# ESP_LoRa_Weather.net
KiCad netlist of a schematic drawn in EAGLE
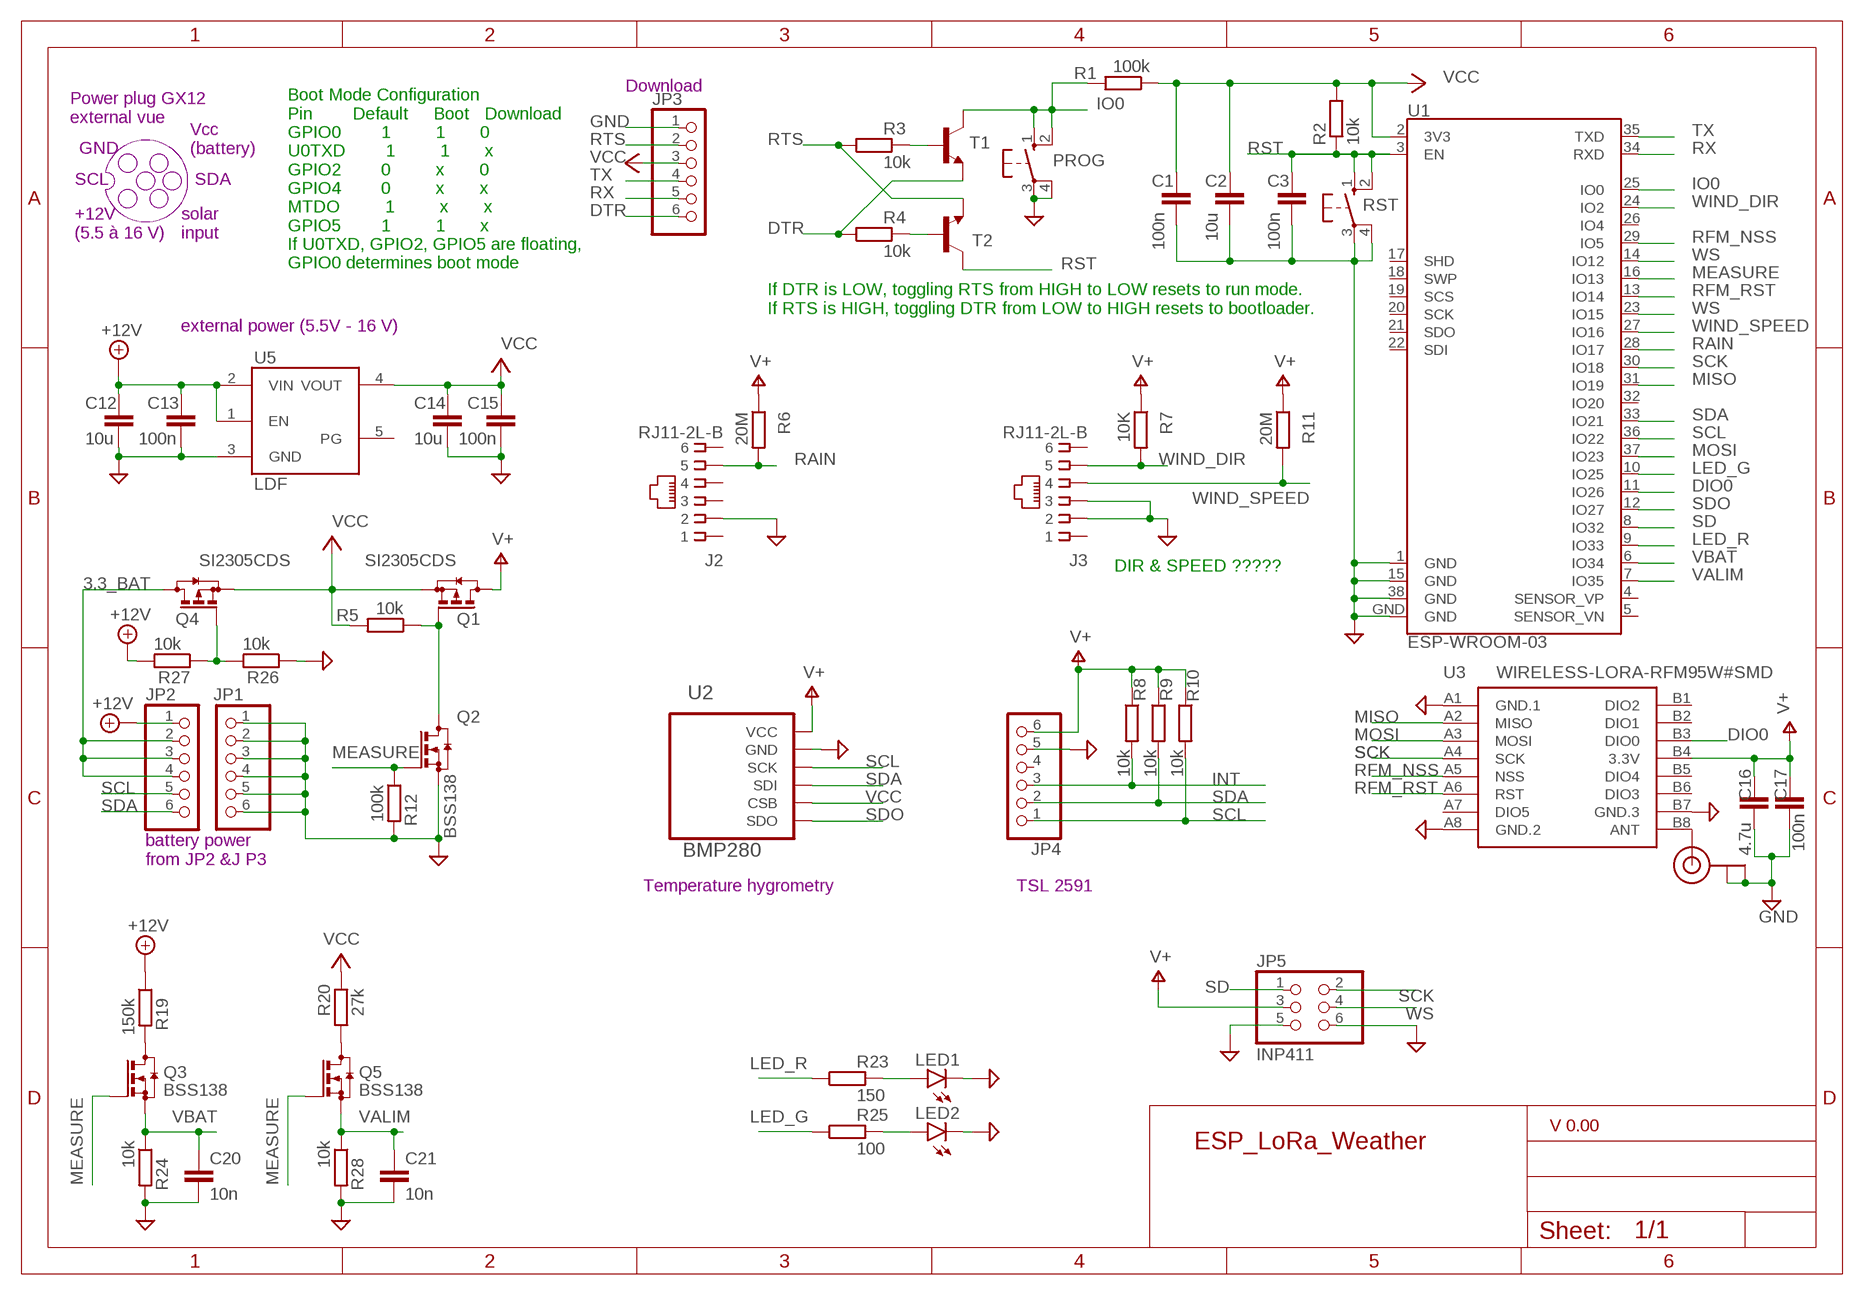
[diagram p0: schematic, sheet 1]

(export (version "E")
  (design (tool "Eeschema 10.0.6"))
  (components
    (comp (ref "C1")
      (value "100n")
      (footprint "eagle-import:C1206")
      (libsource (lib "eagle-import") (part "CC1206"))
    )
    (comp (ref "C2")
      (value "10u")
      (footprint "eagle-import:C1210")
      (libsource (lib "eagle-import") (part "CC1210"))
    )
    (comp (ref "C3")
      (value "100n")
      (footprint "eagle-import:C1206")
      (libsource (lib "eagle-import") (part "CC1206"))
    )
    (comp (ref "C12")
      (value "10u")
      (footprint "eagle-import:C1210")
      (libsource (lib "eagle-import") (part "CC1210"))
    )
    (comp (ref "C13")
      (value "100n")
      (footprint "eagle-import:C1206")
      (libsource (lib "eagle-import") (part "CC1206"))
    )
    (comp (ref "C14")
      (value "10u")
      (footprint "eagle-import:C1210")
      (libsource (lib "eagle-import") (part "CC1210"))
    )
    (comp (ref "C15")
      (value "100n")
      (footprint "eagle-import:C1206")
      (libsource (lib "eagle-import") (part "CC1206"))
    )
    (comp (ref "C16")
      (value "4.7u")
      (footprint "eagle-import:C1210")
      (libsource (lib "eagle-import") (part "CC1210"))
    )
    (comp (ref "C17")
      (value "100n")
      (footprint "eagle-import:C1206")
      (libsource (lib "eagle-import") (part "CC1206"))
    )
    (comp (ref "C20")
      (value "10n")
      (footprint "eagle-import:C1206")
      (libsource (lib "eagle-import") (part "CC1206"))
    )
    (comp (ref "C21")
      (value "10n")
      (footprint "eagle-import:C1206")
      (libsource (lib "eagle-import") (part "CC1206"))
    )
    (comp (ref "J1")
      (value "U.FL")
      (footprint "eagle-import:U.FL")
      (libsource (lib "eagle-import") (part "U.FL"))
    )
    (comp (ref "J2")
      (value "RJ11-2L-B")
      (footprint "eagle-import:RJ11-NO_SHIELD")
      (fields (field (name "MF") "TYCO ELECTRONICS"))
      (libsource (lib "eagle-import") (part "RJ11-2L-B"))
    )
    (comp (ref "J3")
      (value "RJ11-2L-B")
      (footprint "eagle-import:RJ11-NO_SHIELD")
      (fields (field (name "MF") "TYCO ELECTRONICS"))
      (libsource (lib "eagle-import") (part "RJ11-2L-B"))
    )
    (comp (ref "JP1")
      (value "PINHD-1X6")
      (footprint "eagle-import:1X06")
      (libsource (lib "eagle-import") (part "PINHD-1X6"))
    )
    (comp (ref "JP2")
      (value "PINHD-1X6")
      (footprint "eagle-import:1X06")
      (libsource (lib "eagle-import") (part "PINHD-1X6"))
    )
    (comp (ref "JP3")
      (value "PINHD-1X6")
      (footprint "eagle-import:1X06")
      (libsource (lib "eagle-import") (part "PINHD-1X6"))
    )
    (comp (ref "JP4")
      (value "PINHD-1X6")
      (footprint "eagle-import:1X06")
      (libsource (lib "eagle-import") (part "PINHD-1X6"))
    )
    (comp (ref "JP5")
      (value "INP411")
      (footprint "eagle-import:2X03")
      (libsource (lib "eagle-import") (part "PINHD-2X3"))
    )
    (comp (ref "LED1")
      (value "LEDCHIPLED_0805")
      (footprint "eagle-import:CHIPLED_0805")
      (libsource (lib "eagle-import") (part "LEDCHIPLED_0805"))
    )
    (comp (ref "LED2")
      (value "LEDCHIPLED_0805")
      (footprint "eagle-import:CHIPLED_0805")
      (libsource (lib "eagle-import") (part "LEDCHIPLED_0805"))
    )
    (comp (ref "PROG")
      (value "10-XX")
      (footprint "eagle-import:B3F-10XX")
      (fields (field (name "MPN") "B3F-1000"))
      (libsource (lib "eagle-import") (part "10-XX"))
    )
    (comp (ref "Q1")
      (value "SI2305CDS")
      (footprint "eagle-import:SOT23")
      (libsource (lib "eagle-import") (part "SI2305CDS"))
    )
    (comp (ref "Q2")
      (value "BSS138")
      (footprint "eagle-import:SOT23")
      (libsource (lib "eagle-import") (part "BSS138"))
    )
    (comp (ref "Q3")
      (value "BSS138")
      (footprint "eagle-import:SOT23")
      (libsource (lib "eagle-import") (part "BSS138"))
    )
    (comp (ref "Q4")
      (value "SI2305CDS")
      (footprint "eagle-import:SOT23")
      (libsource (lib "eagle-import") (part "SI2305CDS"))
    )
    (comp (ref "Q5")
      (value "BSS138")
      (footprint "eagle-import:SOT23")
      (libsource (lib "eagle-import") (part "BSS138"))
    )
    (comp (ref "R1")
      (value "100k")
      (footprint "eagle-import:R1206")
      (libsource (lib "eagle-import") (part "RR1206"))
    )
    (comp (ref "R2")
      (value "10k")
      (footprint "eagle-import:R1206")
      (libsource (lib "eagle-import") (part "RR1206"))
    )
    (comp (ref "R3")
      (value "10k")
      (footprint "eagle-import:R1206")
      (libsource (lib "eagle-import") (part "RR1206"))
    )
    (comp (ref "R4")
      (value "10k")
      (footprint "eagle-import:R1206")
      (libsource (lib "eagle-import") (part "RR1206"))
    )
    (comp (ref "R5")
      (value "10k")
      (footprint "eagle-import:R1206")
      (libsource (lib "eagle-import") (part "RR1206"))
    )
    (comp (ref "R6")
      (value "20M")
      (footprint "eagle-import:R1206")
      (libsource (lib "eagle-import") (part "RR1206"))
    )
    (comp (ref "R7")
      (value "10K")
      (footprint "eagle-import:R1206")
      (libsource (lib "eagle-import") (part "RR1206"))
    )
    (comp (ref "R8")
      (value "10k")
      (footprint "eagle-import:R1206")
      (libsource (lib "eagle-import") (part "RR1206"))
    )
    (comp (ref "R9")
      (value "10k")
      (footprint "eagle-import:R1206")
      (libsource (lib "eagle-import") (part "RR1206"))
    )
    (comp (ref "R10")
      (value "10k")
      (footprint "eagle-import:R1206")
      (libsource (lib "eagle-import") (part "RR1206"))
    )
    (comp (ref "R11")
      (value "20M")
      (footprint "eagle-import:R1206")
      (libsource (lib "eagle-import") (part "RR1206"))
    )
    (comp (ref "R12")
      (value "100k")
      (footprint "eagle-import:R1206")
      (libsource (lib "eagle-import") (part "RR1206"))
    )
    (comp (ref "R19")
      (value "150k")
      (footprint "eagle-import:R1206")
      (libsource (lib "eagle-import") (part "RR1206"))
    )
    (comp (ref "R20")
      (value "27k")
      (footprint "eagle-import:R1206")
      (libsource (lib "eagle-import") (part "RR1206"))
    )
    (comp (ref "R23")
      (value "150")
      (footprint "eagle-import:R1206")
      (libsource (lib "eagle-import") (part "RR1206"))
    )
    (comp (ref "R24")
      (value "10k")
      (footprint "eagle-import:R1206")
      (libsource (lib "eagle-import") (part "RR1206"))
    )
    (comp (ref "R25")
      (value "100")
      (footprint "eagle-import:R1206")
      (libsource (lib "eagle-import") (part "RR1206"))
    )
    (comp (ref "R26")
      (value "10k")
      (footprint "eagle-import:R1206")
      (libsource (lib "eagle-import") (part "RR1206"))
    )
    (comp (ref "R27")
      (value "10k")
      (footprint "eagle-import:R1206")
      (libsource (lib "eagle-import") (part "RR1206"))
    )
    (comp (ref "R28")
      (value "10k")
      (footprint "eagle-import:R1206")
      (libsource (lib "eagle-import") (part "RR1206"))
    )
    (comp (ref "RST")
      (value "10-XX")
      (footprint "eagle-import:B3F-10XX")
      (fields (field (name "MPN") "B3F-1000"))
      (libsource (lib "eagle-import") (part "10-XX"))
    )
    (comp (ref "T1")
      (value "MMBT2222ALT1-NPN-SOT23-BEC")
      (footprint "eagle-import:SOT23-BEC")
      (libsource (lib "eagle-import") (part "-NPN-SOT23-BECMMBT2222ALT1"))
    )
    (comp (ref "T2")
      (value "MMBT2222ALT1-NPN-SOT23-BEC")
      (footprint "eagle-import:SOT23-BEC")
      (libsource (lib "eagle-import") (part "-NPN-SOT23-BECMMBT2222ALT1"))
    )
    (comp (ref "U1")
      (value "ESP-WROOM-03")
      (footprint "eagle-import:ESP-WROOM-03")
      (libsource (lib "eagle-import") (part "ESP-WROOM-03"))
    )
    (comp (ref "U2")
      (value "BMP280")
      (footprint "eagle-import:BMP280")
      (libsource (lib "eagle-import") (part "BMP280"))
    )
    (comp (ref "U3")
      (value "WIRELESS-LORA-RFM95W#SMD")
      (footprint "eagle-import:WIRELESS-LORA-RFM95W#SMD")
      (libsource (lib "eagle-import") (part "WIRELESS-LORA-RFM95W#SMD"))
    )
    (comp (ref "U5")
      (value "LDF3.3")
      (footprint "eagle-import:PPAK")
      (libsource (lib "eagle-import") (part "LDF3.3"))
    )
  )
  (nets
    (net (code "1") (name "+12V") (class "Default")
      (node (ref "C12") (pin "1") (pinfunction "1_1") (pintype "passive"))
      (node (ref "C13") (pin "1") (pinfunction "1_1") (pintype "passive"))
      (node (ref "JP2") (pin "1") (pinfunction "1_1") (pintype "passive"))
      (node (ref "R19") (pin "1") (pinfunction "1_1") (pintype "passive"))
      (node (ref "R27") (pin "2") (pinfunction "2_2") (pintype "passive"))
      (node (ref "U5") (pin "1") (pinfunction "EN_1") (pintype "input"))
      (node (ref "U5") (pin "2") (pinfunction "VIN_2") (pintype "power_in"))
    )
    (net (code "2") (name "/3.3_BAT") (class "Default")
      (node (ref "JP2") (pin "2") (pinfunction "2_2") (pintype "passive"))
      (node (ref "JP2") (pin "3") (pinfunction "3_3") (pintype "passive"))
      (node (ref "JP2") (pin "4") (pinfunction "4_4") (pintype "passive"))
      (node (ref "Q4") (pin "3") (pinfunction "D_3") (pintype "passive"))
    )
    (net (code "3") (name "/DIO0") (class "Default")
      (node (ref "U1") (pin "11") (pinfunction "IO26_11") (pintype "bidirectional"))
      (node (ref "U3") (pin "B3") (pinfunction "DIO0_B3") (pintype "bidirectional"))
    )
    (net (code "4") (name "/DTR") (class "Default")
      (node (ref "JP3") (pin "6") (pinfunction "6_6") (pintype "passive"))
      (node (ref "R4") (pin "1") (pinfunction "1_1") (pintype "passive"))
      (node (ref "T1") (pin "E") (pinfunction "E_E") (pintype "passive"))
    )
    (net (code "5") (name "/INT") (class "Default")
      (node (ref "JP4") (pin "3") (pinfunction "3_3") (pintype "passive"))
      (node (ref "R8") (pin "2") (pinfunction "2_2") (pintype "passive"))
    )
    (net (code "6") (name "/IO0") (class "Default")
      (node (ref "PROG") (pin "1") (pinfunction "S_1") (pintype "passive"))
      (node (ref "PROG") (pin "2") (pinfunction "S1_2") (pintype "passive"))
      (node (ref "R1") (pin "2") (pinfunction "2_2") (pintype "passive"))
      (node (ref "T1") (pin "C") (pinfunction "C_C") (pintype "passive"))
      (node (ref "U1") (pin "25") (pinfunction "IO0_25") (pintype "bidirectional"))
    )
    (net (code "7") (name "/LED_G") (class "Default")
      (node (ref "R25") (pin "1") (pinfunction "1_1") (pintype "passive"))
      (node (ref "U1") (pin "10") (pinfunction "IO25_10") (pintype "bidirectional"))
    )
    (net (code "8") (name "/LED_R") (class "Default")
      (node (ref "R23") (pin "1") (pinfunction "1_1") (pintype "passive"))
      (node (ref "U1") (pin "9") (pinfunction "IO33_9") (pintype "bidirectional"))
    )
    (net (code "9") (name "/MEASURE") (class "Default")
      (node (ref "Q2") (pin "1") (pinfunction "G_1") (pintype "passive"))
      (node (ref "Q3") (pin "1") (pinfunction "G_1") (pintype "passive"))
      (node (ref "Q5") (pin "1") (pinfunction "G_1") (pintype "passive"))
      (node (ref "R12") (pin "1") (pinfunction "1_1") (pintype "passive"))
      (node (ref "U1") (pin "16") (pinfunction "IO13_16") (pintype "bidirectional"))
    )
    (net (code "10") (name "/MISO") (class "Default")
      (node (ref "U1") (pin "31") (pinfunction "IO19_31") (pintype "bidirectional"))
      (node (ref "U3") (pin "A2") (pinfunction "MISO_A2") (pintype "bidirectional"))
    )
    (net (code "11") (name "/MOSI") (class "Default")
      (node (ref "U1") (pin "37") (pinfunction "IO23_37") (pintype "bidirectional"))
      (node (ref "U3") (pin "A3") (pinfunction "MOSI_A3") (pintype "bidirectional"))
    )
    (net (code "12") (name "/PG") (class "Default")
      (node (ref "U5") (pin "5") (pinfunction "PG_5") (pintype "power_in"))
    )
    (net (code "13") (name "/RAIN") (class "Default")
      (node (ref "J2") (pin "5") (pinfunction "5_5") (pintype "passive"))
      (node (ref "R6") (pin "2") (pinfunction "2_2") (pintype "passive"))
      (node (ref "U1") (pin "28") (pinfunction "IO17_28") (pintype "bidirectional"))
    )
    (net (code "14") (name "/RFM_NSS") (class "Default")
      (node (ref "U1") (pin "29") (pinfunction "IO5_29") (pintype "bidirectional"))
      (node (ref "U3") (pin "A5") (pinfunction "NSS_A5") (pintype "bidirectional"))
    )
    (net (code "15") (name "/RFM_RST") (class "Default")
      (node (ref "U1") (pin "13") (pinfunction "IO14_13") (pintype "bidirectional"))
      (node (ref "U3") (pin "A6") (pinfunction "RST_A6") (pintype "bidirectional"))
    )
    (net (code "16") (name "/RST") (class "Default")
      (node (ref "C3") (pin "1") (pinfunction "1_1") (pintype "passive"))
      (node (ref "R2") (pin "1") (pinfunction "1_1") (pintype "passive"))
      (node (ref "RST") (pin "1") (pinfunction "S_1") (pintype "passive"))
      (node (ref "RST") (pin "2") (pinfunction "S1_2") (pintype "passive"))
      (node (ref "T2") (pin "C") (pinfunction "C_C") (pintype "passive"))
      (node (ref "U1") (pin "3") (pinfunction "EN_3") (pintype "bidirectional"))
    )
    (net (code "17") (name "/RTS") (class "Default")
      (node (ref "JP3") (pin "2") (pinfunction "2_2") (pintype "passive"))
      (node (ref "R3") (pin "1") (pinfunction "1_1") (pintype "passive"))
      (node (ref "T2") (pin "E") (pinfunction "E_E") (pintype "passive"))
    )
    (net (code "18") (name "/RX") (class "Default")
      (node (ref "JP3") (pin "5") (pinfunction "5_5") (pintype "passive"))
      (node (ref "U1") (pin "34") (pinfunction "RXD_34") (pintype "bidirectional"))
    )
    (net (code "19") (name "/SCK") (class "Default")
      (node (ref "JP5") (pin "2") (pinfunction "2_2") (pintype "passive"))
      (node (ref "U1") (pin "30") (pinfunction "IO18_30") (pintype "bidirectional"))
      (node (ref "U3") (pin "A4") (pinfunction "SCK_A4") (pintype "bidirectional"))
    )
    (net (code "20") (name "/SCL") (class "Default")
      (node (ref "JP2") (pin "5") (pinfunction "5_5") (pintype "passive"))
      (node (ref "JP4") (pin "1") (pinfunction "1_1") (pintype "passive"))
      (node (ref "R10") (pin "2") (pinfunction "2_2") (pintype "passive"))
      (node (ref "U1") (pin "36") (pinfunction "IO22_36") (pintype "bidirectional"))
      (node (ref "U2") (pin "SCK") (pinfunction "SCK_SCK") (pintype "bidirectional"))
    )
    (net (code "21") (name "/SD") (class "Default")
      (node (ref "JP5") (pin "1") (pinfunction "1_1") (pintype "passive"))
      (node (ref "U1") (pin "8") (pinfunction "IO32_8") (pintype "bidirectional"))
    )
    (net (code "22") (name "/SDA") (class "Default")
      (node (ref "JP2") (pin "6") (pinfunction "6_6") (pintype "passive"))
      (node (ref "JP4") (pin "2") (pinfunction "2_2") (pintype "passive"))
      (node (ref "R9") (pin "2") (pinfunction "2_2") (pintype "passive"))
      (node (ref "U1") (pin "33") (pinfunction "IO21_33") (pintype "bidirectional"))
      (node (ref "U2") (pin "SDI") (pinfunction "SDI_SDI") (pintype "bidirectional"))
    )
    (net (code "23") (name "/SDO") (class "Default")
      (node (ref "U1") (pin "12") (pinfunction "IO27_12") (pintype "bidirectional"))
      (node (ref "U2") (pin "SD0") (pinfunction "SDO_SD0") (pintype "bidirectional"))
    )
    (net (code "24") (name "/TX") (class "Default")
      (node (ref "JP3") (pin "4") (pinfunction "4_4") (pintype "passive"))
      (node (ref "U1") (pin "35") (pinfunction "TXD_35") (pintype "bidirectional"))
    )
    (net (code "25") (name "/VALIM") (class "Default")
      (node (ref "C21") (pin "1") (pinfunction "1_1") (pintype "passive"))
      (node (ref "Q5") (pin "2") (pinfunction "S_2") (pintype "passive"))
      (node (ref "R28") (pin "1") (pinfunction "1_1") (pintype "passive"))
      (node (ref "U1") (pin "7") (pinfunction "IO35_7") (pintype "bidirectional"))
    )
    (net (code "26") (name "/VBAT") (class "Default")
      (node (ref "C20") (pin "1") (pinfunction "1_1") (pintype "passive"))
      (node (ref "Q3") (pin "2") (pinfunction "S_2") (pintype "passive"))
      (node (ref "R24") (pin "1") (pinfunction "1_1") (pintype "passive"))
      (node (ref "U1") (pin "6") (pinfunction "IO34_6") (pintype "bidirectional"))
    )
    (net (code "27") (name "/WIND_DIR") (class "Default")
      (node (ref "J3") (pin "5") (pinfunction "5_5") (pintype "passive"))
      (node (ref "R7") (pin "2") (pinfunction "2_2") (pintype "passive"))
      (node (ref "U1") (pin "24") (pinfunction "IO2_24") (pintype "bidirectional"))
    )
    (net (code "28") (name "/WIND_SPEED") (class "Default")
      (node (ref "J3") (pin "4") (pinfunction "4_4") (pintype "passive"))
      (node (ref "R11") (pin "2") (pinfunction "2_2") (pintype "passive"))
      (node (ref "U1") (pin "27") (pinfunction "IO16_27") (pintype "bidirectional"))
    )
    (net (code "29") (name "/WS") (class "Default")
      (node (ref "JP5") (pin "4") (pinfunction "4_4") (pintype "passive"))
      (node (ref "U1") (pin "14") (pinfunction "IO12_14") (pintype "bidirectional"))
      (node (ref "U1") (pin "23") (pinfunction "IO15_23") (pintype "bidirectional"))
    )
    (net (code "30") (name "GND") (class "Default")
      (node (ref "C1") (pin "2") (pinfunction "2_2") (pintype "passive"))
      (node (ref "C12") (pin "2") (pinfunction "2_2") (pintype "passive"))
      (node (ref "C13") (pin "2") (pinfunction "2_2") (pintype "passive"))
      (node (ref "C14") (pin "2") (pinfunction "2_2") (pintype "passive"))
      (node (ref "C15") (pin "2") (pinfunction "2_2") (pintype "passive"))
      (node (ref "C16") (pin "2") (pinfunction "2_2") (pintype "passive"))
      (node (ref "C17") (pin "2") (pinfunction "2_2") (pintype "passive"))
      (node (ref "C2") (pin "2") (pinfunction "2_2") (pintype "passive"))
      (node (ref "C20") (pin "2") (pinfunction "2_2") (pintype "passive"))
      (node (ref "C21") (pin "2") (pinfunction "2_2") (pintype "passive"))
      (node (ref "C3") (pin "2") (pinfunction "2_2") (pintype "passive"))
      (node (ref "J1") (pin "1") (pinfunction "GND_1") (pintype "passive"))
      (node (ref "J1") (pin "2") (pinfunction "GND_2") (pintype "passive"))
      (node (ref "J2") (pin "2") (pinfunction "2_2") (pintype "passive"))
      (node (ref "J3") (pin "2") (pinfunction "2_2") (pintype "passive"))
      (node (ref "J3") (pin "3") (pinfunction "3_3") (pintype "passive"))
      (node (ref "JP1") (pin "1") (pinfunction "1_1") (pintype "passive"))
      (node (ref "JP1") (pin "2") (pinfunction "2_2") (pintype "passive"))
      (node (ref "JP1") (pin "3") (pinfunction "3_3") (pintype "passive"))
      (node (ref "JP1") (pin "4") (pinfunction "4_4") (pintype "passive"))
      (node (ref "JP1") (pin "5") (pinfunction "5_5") (pintype "passive"))
      (node (ref "JP1") (pin "6") (pinfunction "6_6") (pintype "passive"))
      (node (ref "JP3") (pin "1") (pinfunction "1_1") (pintype "passive"))
      (node (ref "JP4") (pin "5") (pinfunction "5_5") (pintype "passive"))
      (node (ref "JP5") (pin "5") (pinfunction "5_5") (pintype "passive"))
      (node (ref "JP5") (pin "6") (pinfunction "6_6") (pintype "passive"))
      (node (ref "LED1") (pin "C") (pinfunction "C_C") (pintype "passive"))
      (node (ref "LED2") (pin "C") (pinfunction "C_C") (pintype "passive"))
      (node (ref "PROG") (pin "3") (pinfunction "P_3") (pintype "passive"))
      (node (ref "PROG") (pin "4") (pinfunction "P1_4") (pintype "passive"))
      (node (ref "Q2") (pin "2") (pinfunction "S_2") (pintype "passive"))
      (node (ref "R12") (pin "2") (pinfunction "2_2") (pintype "passive"))
      (node (ref "R24") (pin "2") (pinfunction "2_2") (pintype "passive"))
      (node (ref "R26") (pin "1") (pinfunction "1_1") (pintype "passive"))
      (node (ref "R28") (pin "2") (pinfunction "2_2") (pintype "passive"))
      (node (ref "RST") (pin "3") (pinfunction "P_3") (pintype "passive"))
      (node (ref "RST") (pin "4") (pinfunction "P1_4") (pintype "passive"))
      (node (ref "U1") (pin "1") (pinfunction "GND_1") (pintype "bidirectional"))
      (node (ref "U1") (pin "15") (pinfunction "GND_15") (pintype "bidirectional"))
      (node (ref "U1") (pin "38") (pinfunction "GND_38") (pintype "bidirectional"))
      (node (ref "U1") (pin "GND") (pinfunction "GND_GND") (pintype "bidirectional"))
      (node (ref "U2") (pin "GND") (pinfunction "GND_GND") (pintype "power_in"))
      (node (ref "U3") (pin "A1") (pinfunction "GND.1_A1") (pintype "power_in"))
      (node (ref "U3") (pin "A8") (pinfunction "GND.2_A8") (pintype "power_in"))
      (node (ref "U3") (pin "B7") (pinfunction "GND.3_B7") (pintype "power_in"))
      (node (ref "U5") (pin "3") (pinfunction "GND_3") (pintype "power_in"))
    )
    (net (code "31") (name "Net-(J1-SIGNAL)") (class "Default")
      (node (ref "J1") (pin "3") (pinfunction "SIGNAL_3") (pintype "passive"))
      (node (ref "U3") (pin "B8") (pinfunction "ANT_B8") (pintype "passive"))
    )
    (net (code "32") (name "Net-(LED1-PadA)") (class "Default")
      (node (ref "LED1") (pin "A") (pinfunction "A_A") (pintype "passive"))
      (node (ref "R23") (pin "2") (pinfunction "2_2") (pintype "passive"))
    )
    (net (code "33") (name "Net-(LED2-PadA)") (class "Default")
      (node (ref "LED2") (pin "A") (pinfunction "A_A") (pintype "passive"))
      (node (ref "R25") (pin "2") (pinfunction "2_2") (pintype "passive"))
    )
    (net (code "34") (name "Net-(Q1-G)") (class "Default")
      (node (ref "Q1") (pin "1") (pinfunction "G_1") (pintype "passive"))
      (node (ref "Q2") (pin "3") (pinfunction "D_3") (pintype "passive"))
      (node (ref "R5") (pin "1") (pinfunction "1_1") (pintype "passive"))
    )
    (net (code "35") (name "Net-(Q3-D)") (class "Default")
      (node (ref "Q3") (pin "3") (pinfunction "D_3") (pintype "passive"))
      (node (ref "R19") (pin "2") (pinfunction "2_2") (pintype "passive"))
    )
    (net (code "36") (name "Net-(Q4-G)") (class "Default")
      (node (ref "Q4") (pin "1") (pinfunction "G_1") (pintype "passive"))
      (node (ref "R26") (pin "2") (pinfunction "2_2") (pintype "passive"))
      (node (ref "R27") (pin "1") (pinfunction "1_1") (pintype "passive"))
    )
    (net (code "37") (name "Net-(Q5-D)") (class "Default")
      (node (ref "Q5") (pin "3") (pinfunction "D_3") (pintype "passive"))
      (node (ref "R20") (pin "1") (pinfunction "1_1") (pintype "passive"))
    )
    (net (code "38") (name "Net-(R3-Pad2)") (class "Default")
      (node (ref "R3") (pin "2") (pinfunction "2_2") (pintype "passive"))
      (node (ref "T1") (pin "B") (pinfunction "B_B") (pintype "passive"))
    )
    (net (code "39") (name "Net-(R4-Pad2)") (class "Default")
      (node (ref "R4") (pin "2") (pinfunction "2_2") (pintype "passive"))
      (node (ref "T2") (pin "B") (pinfunction "B_B") (pintype "passive"))
    )
    (net (code "40") (name "V+") (class "Default")
      (node (ref "C16") (pin "1") (pinfunction "1_1") (pintype "passive"))
      (node (ref "C17") (pin "1") (pinfunction "1_1") (pintype "passive"))
      (node (ref "JP4") (pin "6") (pinfunction "6_6") (pintype "passive"))
      (node (ref "JP5") (pin "3") (pinfunction "3_3") (pintype "passive"))
      (node (ref "Q1") (pin "3") (pinfunction "D_3") (pintype "passive"))
      (node (ref "R10") (pin "1") (pinfunction "1_1") (pintype "passive"))
      (node (ref "R11") (pin "1") (pinfunction "1_1") (pintype "passive"))
      (node (ref "R6") (pin "1") (pinfunction "1_1") (pintype "passive"))
      (node (ref "R7") (pin "1") (pinfunction "1_1") (pintype "passive"))
      (node (ref "R8") (pin "1") (pinfunction "1_1") (pintype "passive"))
      (node (ref "R9") (pin "1") (pinfunction "1_1") (pintype "passive"))
      (node (ref "U2") (pin "VCC") (pinfunction "VCC_VCC") (pintype "power_in"))
      (node (ref "U3") (pin "B4") (pinfunction "3.3V_B4") (pintype "power_in"))
    )
    (net (code "41") (name "VCC") (class "Default")
      (node (ref "C1") (pin "1") (pinfunction "1_1") (pintype "passive"))
      (node (ref "C14") (pin "1") (pinfunction "1_1") (pintype "passive"))
      (node (ref "C15") (pin "1") (pinfunction "1_1") (pintype "passive"))
      (node (ref "C2") (pin "1") (pinfunction "1_1") (pintype "passive"))
      (node (ref "JP3") (pin "3") (pinfunction "3_3") (pintype "passive"))
      (node (ref "Q1") (pin "2") (pinfunction "S_2") (pintype "passive"))
      (node (ref "Q4") (pin "2") (pinfunction "S_2") (pintype "passive"))
      (node (ref "R1") (pin "1") (pinfunction "1_1") (pintype "passive"))
      (node (ref "R2") (pin "2") (pinfunction "2_2") (pintype "passive"))
      (node (ref "R20") (pin "2") (pinfunction "2_2") (pintype "passive"))
      (node (ref "R5") (pin "2") (pinfunction "2_2") (pintype "passive"))
      (node (ref "U1") (pin "2") (pinfunction "3V3_2") (pintype "bidirectional"))
      (node (ref "U2") (pin "CSB") (pinfunction "CSB_CSB") (pintype "bidirectional"))
      (node (ref "U5") (pin "4") (pinfunction "VOUT_4") (pintype "power_in"))
    )
    (net (code "42") (name "unconnected-(J2-Pad1)") (class "Default")
      (node (ref "J2") (pin "1") (pinfunction "1_1") (pintype "passive"))
    )
    (net (code "43") (name "unconnected-(J2-Pad3)") (class "Default")
      (node (ref "J2") (pin "3") (pinfunction "3_3") (pintype "passive"))
    )
    (net (code "44") (name "unconnected-(J2-Pad4)") (class "Default")
      (node (ref "J2") (pin "4") (pinfunction "4_4") (pintype "passive"))
    )
    (net (code "45") (name "unconnected-(J2-Pad6)") (class "Default")
      (node (ref "J2") (pin "6") (pinfunction "6_6") (pintype "passive"))
    )
    (net (code "46") (name "unconnected-(J3-Pad1)") (class "Default")
      (node (ref "J3") (pin "1") (pinfunction "1_1") (pintype "passive"))
    )
    (net (code "47") (name "unconnected-(J3-Pad6)") (class "Default")
      (node (ref "J3") (pin "6") (pinfunction "6_6") (pintype "passive"))
    )
    (net (code "48") (name "unconnected-(JP4-Pad4)") (class "Default")
      (node (ref "JP4") (pin "4") (pinfunction "4_4") (pintype "passive"))
    )
    (net (code "49") (name "unconnected-(U1-IO4-Pad26)") (class "Default")
      (node (ref "U1") (pin "26") (pinfunction "IO4_26") (pintype "bidirectional"))
    )
    (net (code "50") (name "unconnected-(U1-IO20-Pad32)") (class "Default")
      (node (ref "U1") (pin "32") (pinfunction "IO20_32") (pintype "bidirectional"))
    )
    (net (code "51") (name "unconnected-(U1-SCK-Pad20)") (class "Default")
      (node (ref "U1") (pin "20") (pinfunction "SCK_20") (pintype "bidirectional"))
    )
    (net (code "52") (name "unconnected-(U1-SCS-Pad19)") (class "Default")
      (node (ref "U1") (pin "19") (pinfunction "SCS_19") (pintype "bidirectional"))
    )
    (net (code "53") (name "unconnected-(U1-SDI-Pad22)") (class "Default")
      (node (ref "U1") (pin "22") (pinfunction "SDI_22") (pintype "bidirectional"))
    )
    (net (code "54") (name "unconnected-(U1-SDO-Pad21)") (class "Default")
      (node (ref "U1") (pin "21") (pinfunction "SDO_21") (pintype "bidirectional"))
    )
    (net (code "55") (name "unconnected-(U1-SENSOR_VN-Pad5)") (class "Default")
      (node (ref "U1") (pin "5") (pinfunction "SENSOR_VN_5") (pintype "bidirectional"))
    )
    (net (code "56") (name "unconnected-(U1-SENSOR_VP-Pad4)") (class "Default")
      (node (ref "U1") (pin "4") (pinfunction "SENSOR_VP_4") (pintype "bidirectional"))
    )
    (net (code "57") (name "unconnected-(U1-SHD-Pad17)") (class "Default")
      (node (ref "U1") (pin "17") (pinfunction "SHD_17") (pintype "bidirectional"))
    )
    (net (code "58") (name "unconnected-(U1-SWP-Pad18)") (class "Default")
      (node (ref "U1") (pin "18") (pinfunction "SWP_18") (pintype "bidirectional"))
    )
    (net (code "59") (name "unconnected-(U3-DIO1-PadB2)") (class "Default")
      (node (ref "U3") (pin "B2") (pinfunction "DIO1_B2") (pintype "bidirectional"))
    )
    (net (code "60") (name "unconnected-(U3-DIO2-PadB1)") (class "Default")
      (node (ref "U3") (pin "B1") (pinfunction "DIO2_B1") (pintype "bidirectional"))
    )
    (net (code "61") (name "unconnected-(U3-DIO3-PadB6)") (class "Default")
      (node (ref "U3") (pin "B6") (pinfunction "DIO3_B6") (pintype "bidirectional"))
    )
    (net (code "62") (name "unconnected-(U3-DIO4-PadB5)") (class "Default")
      (node (ref "U3") (pin "B5") (pinfunction "DIO4_B5") (pintype "bidirectional"))
    )
    (net (code "63") (name "unconnected-(U3-DIO5-PadA7)") (class "Default")
      (node (ref "U3") (pin "A7") (pinfunction "DIO5_A7") (pintype "bidirectional"))
    )
  )
)
